# source_eagle.net
KiCad netlist of a schematic drawn in EAGLE
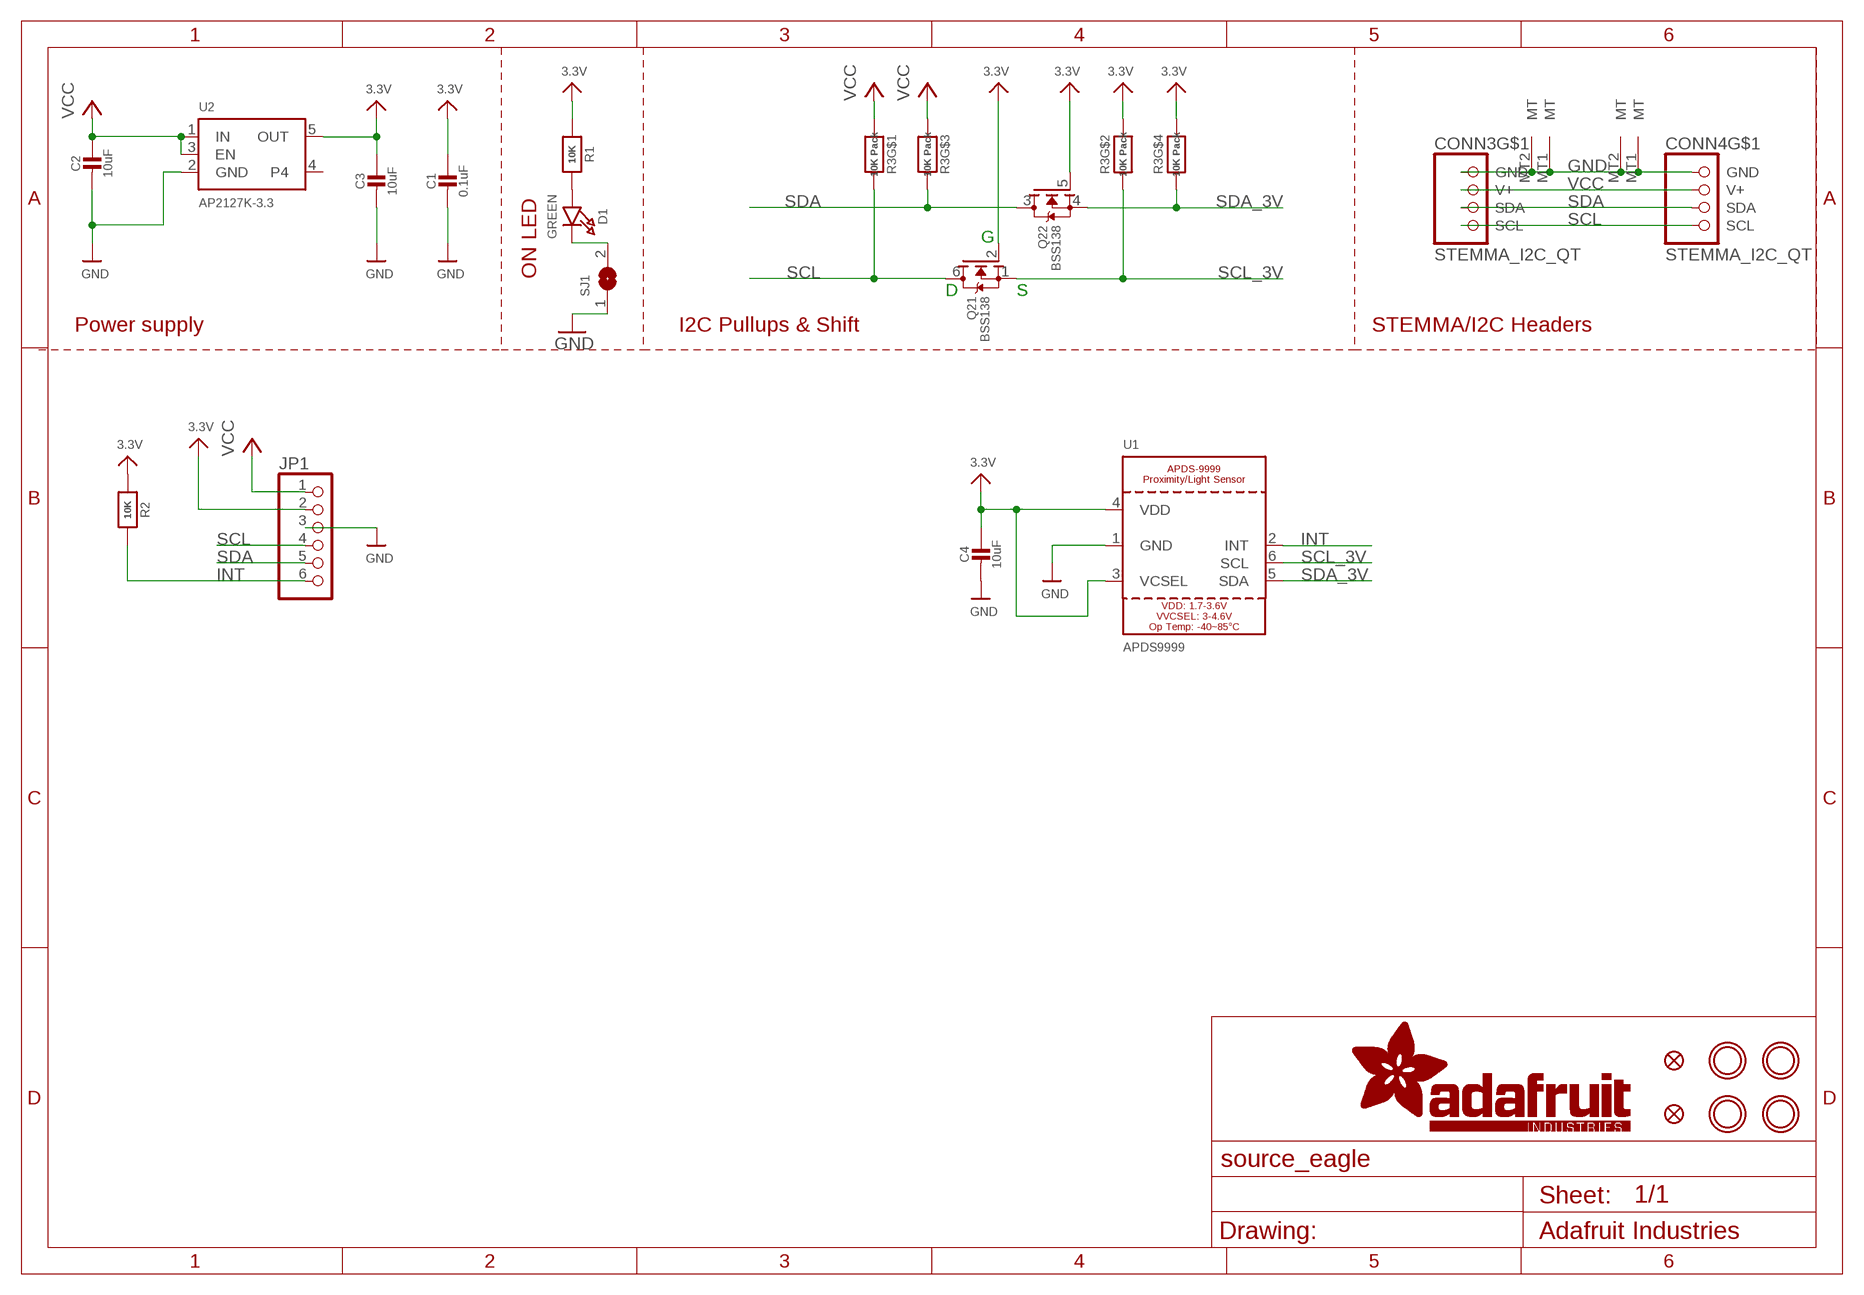
[diagram p0: schematic, sheet 1]

(export (version "E")
  (design (tool "Eeschema 10.0.6"))
  (components
    (comp (ref "C1")
      (value "0.1uF")
      (footprint "eagle-import:0603-NO")
      (libsource (lib "eagle-import") (part "CAP_CERAMIC0603_NO"))
    )
    (comp (ref "C2")
      (value "10uF")
      (footprint "eagle-import:0805-NO")
      (libsource (lib "eagle-import") (part "CAP_CERAMIC0805-NOOUTLINE"))
    )
    (comp (ref "C3")
      (value "10uF")
      (footprint "eagle-import:0805-NO")
      (libsource (lib "eagle-import") (part "CAP_CERAMIC0805-NOOUTLINE"))
    )
    (comp (ref "C4")
      (value "10uF")
      (footprint "eagle-import:0805-NO")
      (libsource (lib "eagle-import") (part "CAP_CERAMIC0805-NOOUTLINE"))
    )
    (comp (ref "CONN3")
      (value "STEMMA_I2C_QT")
      (footprint "eagle-import:JST_SH4")
      (libsource (lib "eagle-import") (part "STEMMA_I2C_QT"))
    )
    (comp (ref "CONN4")
      (value "STEMMA_I2C_QT")
      (footprint "eagle-import:JST_SH4")
      (libsource (lib "eagle-import") (part "STEMMA_I2C_QT"))
    )
    (comp (ref "D1")
      (value "GREEN")
      (footprint "eagle-import:CHIPLED_0603_NOOUTLINE")
      (libsource (lib "eagle-import") (part "LED0603_NOOUTLINE"))
    )
    (comp (ref "FID3")
      (value "FIDUCIAL_0.5MM")
      (footprint "eagle-import:FIDUCIAL_0.5MM")
      (libsource (lib "eagle-import") (part "FIDUCIAL_0.5MM"))
    )
    (comp (ref "FID4")
      (value "FIDUCIAL_0.5MM")
      (footprint "eagle-import:FIDUCIAL_0.5MM")
      (libsource (lib "eagle-import") (part "FIDUCIAL_0.5MM"))
    )
    (comp (ref "JP1")
      (value "HEADER-1X670MIL")
      (footprint "eagle-import:1X06_ROUND_70")
      (libsource (lib "eagle-import") (part "HEADER-1X670MIL"))
    )
    (comp (ref "Q2")
      (value "BSS138")
      (footprint "eagle-import:SOT363")
      (libsource (lib "eagle-import") (part "MOSFET-N_DUAL"))
    )
    (comp (ref "R1")
      (value "10K")
      (footprint "eagle-import:0603-NO")
      (libsource (lib "eagle-import") (part "RESISTOR_0603_NOOUT"))
    )
    (comp (ref "R2")
      (value "10K")
      (footprint "eagle-import:0603-NO")
      (libsource (lib "eagle-import") (part "RESISTOR_0603_NOOUT"))
    )
    (comp (ref "R3")
      (value "10K Pack")
      (footprint "eagle-import:RESPACK_4X0603")
      (libsource (lib "eagle-import") (part "RESISTOR_4PACK"))
    )
    (comp (ref "SJ1")
      (value "SOLDERJUMPERCLOSED")
      (footprint "eagle-import:SOLDERJUMPER_CLOSEDWIRE")
      (libsource (lib "eagle-import") (part "SOLDERJUMPERCLOSED"))
    )
    (comp (ref "U$1")
      (value "MOUNTINGHOLE2.5")
      (footprint "eagle-import:MOUNTINGHOLE_2.5_PLATED")
      (libsource (lib "eagle-import") (part "MOUNTINGHOLE2.5"))
    )
    (comp (ref "U$17")
      (value "MOUNTINGHOLE2.5")
      (footprint "eagle-import:MOUNTINGHOLE_2.5_PLATED")
      (libsource (lib "eagle-import") (part "MOUNTINGHOLE2.5"))
    )
    (comp (ref "U$19")
      (value "MOUNTINGHOLE2.5")
      (footprint "eagle-import:MOUNTINGHOLE_2.5_PLATED")
      (libsource (lib "eagle-import") (part "MOUNTINGHOLE2.5"))
    )
    (comp (ref "U$21")
      (value "MOUNTINGHOLE2.5")
      (footprint "eagle-import:MOUNTINGHOLE_2.5_PLATED")
      (libsource (lib "eagle-import") (part "MOUNTINGHOLE2.5"))
    )
    (comp (ref "U1")
      (value "APDS9999")
      (footprint "eagle-import:APDS-9999")
      (libsource (lib "eagle-import") (part "APDS-9999"))
    )
    (comp (ref "U2")
      (value "AP2127K-3.3")
      (footprint "eagle-import:SOT23-5")
      (libsource (lib "eagle-import") (part "VREG_SOT23-5"))
    )
  )
  (nets
    (net (code "1") (name "/INT") (class "Default")
      (node (ref "JP1") (pin "6") (pinfunction "6_6") (pintype "passive"))
      (node (ref "R2") (pin "2") (pinfunction "2_2") (pintype "passive"))
      (node (ref "U1") (pin "2") (pinfunction "INT_2") (pintype "output"))
    )
    (net (code "2") (name "/SCL") (class "Default")
      (node (ref "CONN3") (pin "4") (pinfunction "SCL_4") (pintype "passive"))
      (node (ref "CONN4") (pin "4") (pinfunction "SCL_4") (pintype "passive"))
      (node (ref "JP1") (pin "4") (pinfunction "4_4") (pintype "passive"))
      (node (ref "Q2") (pin "6") (pinfunction "D_6") (pintype "bidirectional"))
      (node (ref "R3") (pin "8") (pinfunction "2_8") (pintype "passive"))
    )
    (net (code "3") (name "/SCL_3V") (class "Default")
      (node (ref "Q2") (pin "1") (pinfunction "S_1") (pintype "bidirectional"))
      (node (ref "R3") (pin "7") (pinfunction "2_7") (pintype "passive"))
      (node (ref "U1") (pin "6") (pinfunction "SCL_6") (pintype "input"))
    )
    (net (code "4") (name "/SDA") (class "Default")
      (node (ref "CONN3") (pin "3") (pinfunction "SDA_3") (pintype "passive"))
      (node (ref "CONN4") (pin "3") (pinfunction "SDA_3") (pintype "passive"))
      (node (ref "JP1") (pin "5") (pinfunction "5_5") (pintype "passive"))
      (node (ref "Q2") (pin "3") (pinfunction "D_3") (pintype "bidirectional"))
      (node (ref "R3") (pin "6") (pinfunction "2_6") (pintype "passive"))
    )
    (net (code "5") (name "/SDA_3V") (class "Default")
      (node (ref "Q2") (pin "4") (pinfunction "S_4") (pintype "bidirectional"))
      (node (ref "R3") (pin "5") (pinfunction "2_5") (pintype "passive"))
      (node (ref "U1") (pin "5") (pinfunction "SDA_5") (pintype "bidirectional"))
    )
    (net (code "6") (name "3.3V") (class "Default")
      (node (ref "C1") (pin "1") (pinfunction "1_1") (pintype "passive"))
      (node (ref "C3") (pin "1") (pinfunction "1_1") (pintype "passive"))
      (node (ref "C4") (pin "1") (pinfunction "1_1") (pintype "passive"))
      (node (ref "JP1") (pin "2") (pinfunction "2_2") (pintype "passive"))
      (node (ref "Q2") (pin "2") (pinfunction "G_2") (pintype "bidirectional"))
      (node (ref "Q2") (pin "5") (pinfunction "G_5") (pintype "bidirectional"))
      (node (ref "R1") (pin "1") (pinfunction "1_1") (pintype "passive"))
      (node (ref "R2") (pin "1") (pinfunction "1_1") (pintype "passive"))
      (node (ref "R3") (pin "2") (pinfunction "1_2") (pintype "passive"))
      (node (ref "R3") (pin "4") (pinfunction "1_4") (pintype "passive"))
      (node (ref "U1") (pin "3") (pinfunction "VCSEL_3") (pintype "power_in"))
      (node (ref "U1") (pin "4") (pinfunction "VDD_4") (pintype "power_in"))
      (node (ref "U2") (pin "5") (pinfunction "OUT_5") (pintype "power_in"))
    )
    (net (code "7") (name "GND") (class "Default")
      (node (ref "C1") (pin "2") (pinfunction "2_2") (pintype "passive"))
      (node (ref "C2") (pin "2") (pinfunction "2_2") (pintype "passive"))
      (node (ref "C3") (pin "2") (pinfunction "2_2") (pintype "passive"))
      (node (ref "C4") (pin "2") (pinfunction "2_2") (pintype "passive"))
      (node (ref "CONN3") (pin "1") (pinfunction "GND_1") (pintype "passive"))
      (node (ref "CONN3") (pin "MT1") (pinfunction "MT_MT1") (pintype "bidirectional"))
      (node (ref "CONN3") (pin "MT2") (pinfunction "MT_MT2") (pintype "bidirectional"))
      (node (ref "CONN4") (pin "1") (pinfunction "GND_1") (pintype "passive"))
      (node (ref "CONN4") (pin "MT1") (pinfunction "MT_MT1") (pintype "bidirectional"))
      (node (ref "CONN4") (pin "MT2") (pinfunction "MT_MT2") (pintype "bidirectional"))
      (node (ref "JP1") (pin "3") (pinfunction "3_3") (pintype "passive"))
      (node (ref "SJ1") (pin "1") (pinfunction "1_1") (pintype "passive"))
      (node (ref "U1") (pin "1") (pinfunction "GND_1") (pintype "power_in"))
      (node (ref "U2") (pin "2") (pinfunction "GND_2") (pintype "power_in"))
    )
    (net (code "8") (name "Net-(D1-PadA)") (class "Default")
      (node (ref "D1") (pin "A") (pinfunction "A_A") (pintype "passive"))
      (node (ref "R1") (pin "2") (pinfunction "2_2") (pintype "passive"))
    )
    (net (code "9") (name "Net-(D1-PadC)") (class "Default")
      (node (ref "D1") (pin "C") (pinfunction "C_C") (pintype "passive"))
      (node (ref "SJ1") (pin "2") (pinfunction "2_2") (pintype "passive"))
    )
    (net (code "10") (name "VCC") (class "Default")
      (node (ref "C2") (pin "1") (pinfunction "1_1") (pintype "passive"))
      (node (ref "CONN3") (pin "2") (pinfunction "V+_2") (pintype "passive"))
      (node (ref "CONN4") (pin "2") (pinfunction "V+_2") (pintype "passive"))
      (node (ref "JP1") (pin "1") (pinfunction "1_1") (pintype "passive"))
      (node (ref "R3") (pin "1") (pinfunction "1_1") (pintype "passive"))
      (node (ref "R3") (pin "3") (pinfunction "1_3") (pintype "passive"))
      (node (ref "U2") (pin "1") (pinfunction "IN_1") (pintype "power_in"))
      (node (ref "U2") (pin "3") (pinfunction "EN_3") (pintype "input"))
    )
    (net (code "11") (name "unconnected-(U2-P4-Pad4)") (class "Default")
      (node (ref "U2") (pin "4") (pinfunction "P4_4") (pintype "bidirectional"))
    )
  )
)
